# J_SD_KEYPAD.net
KiCad netlist of a schematic drawn in Altium Designer
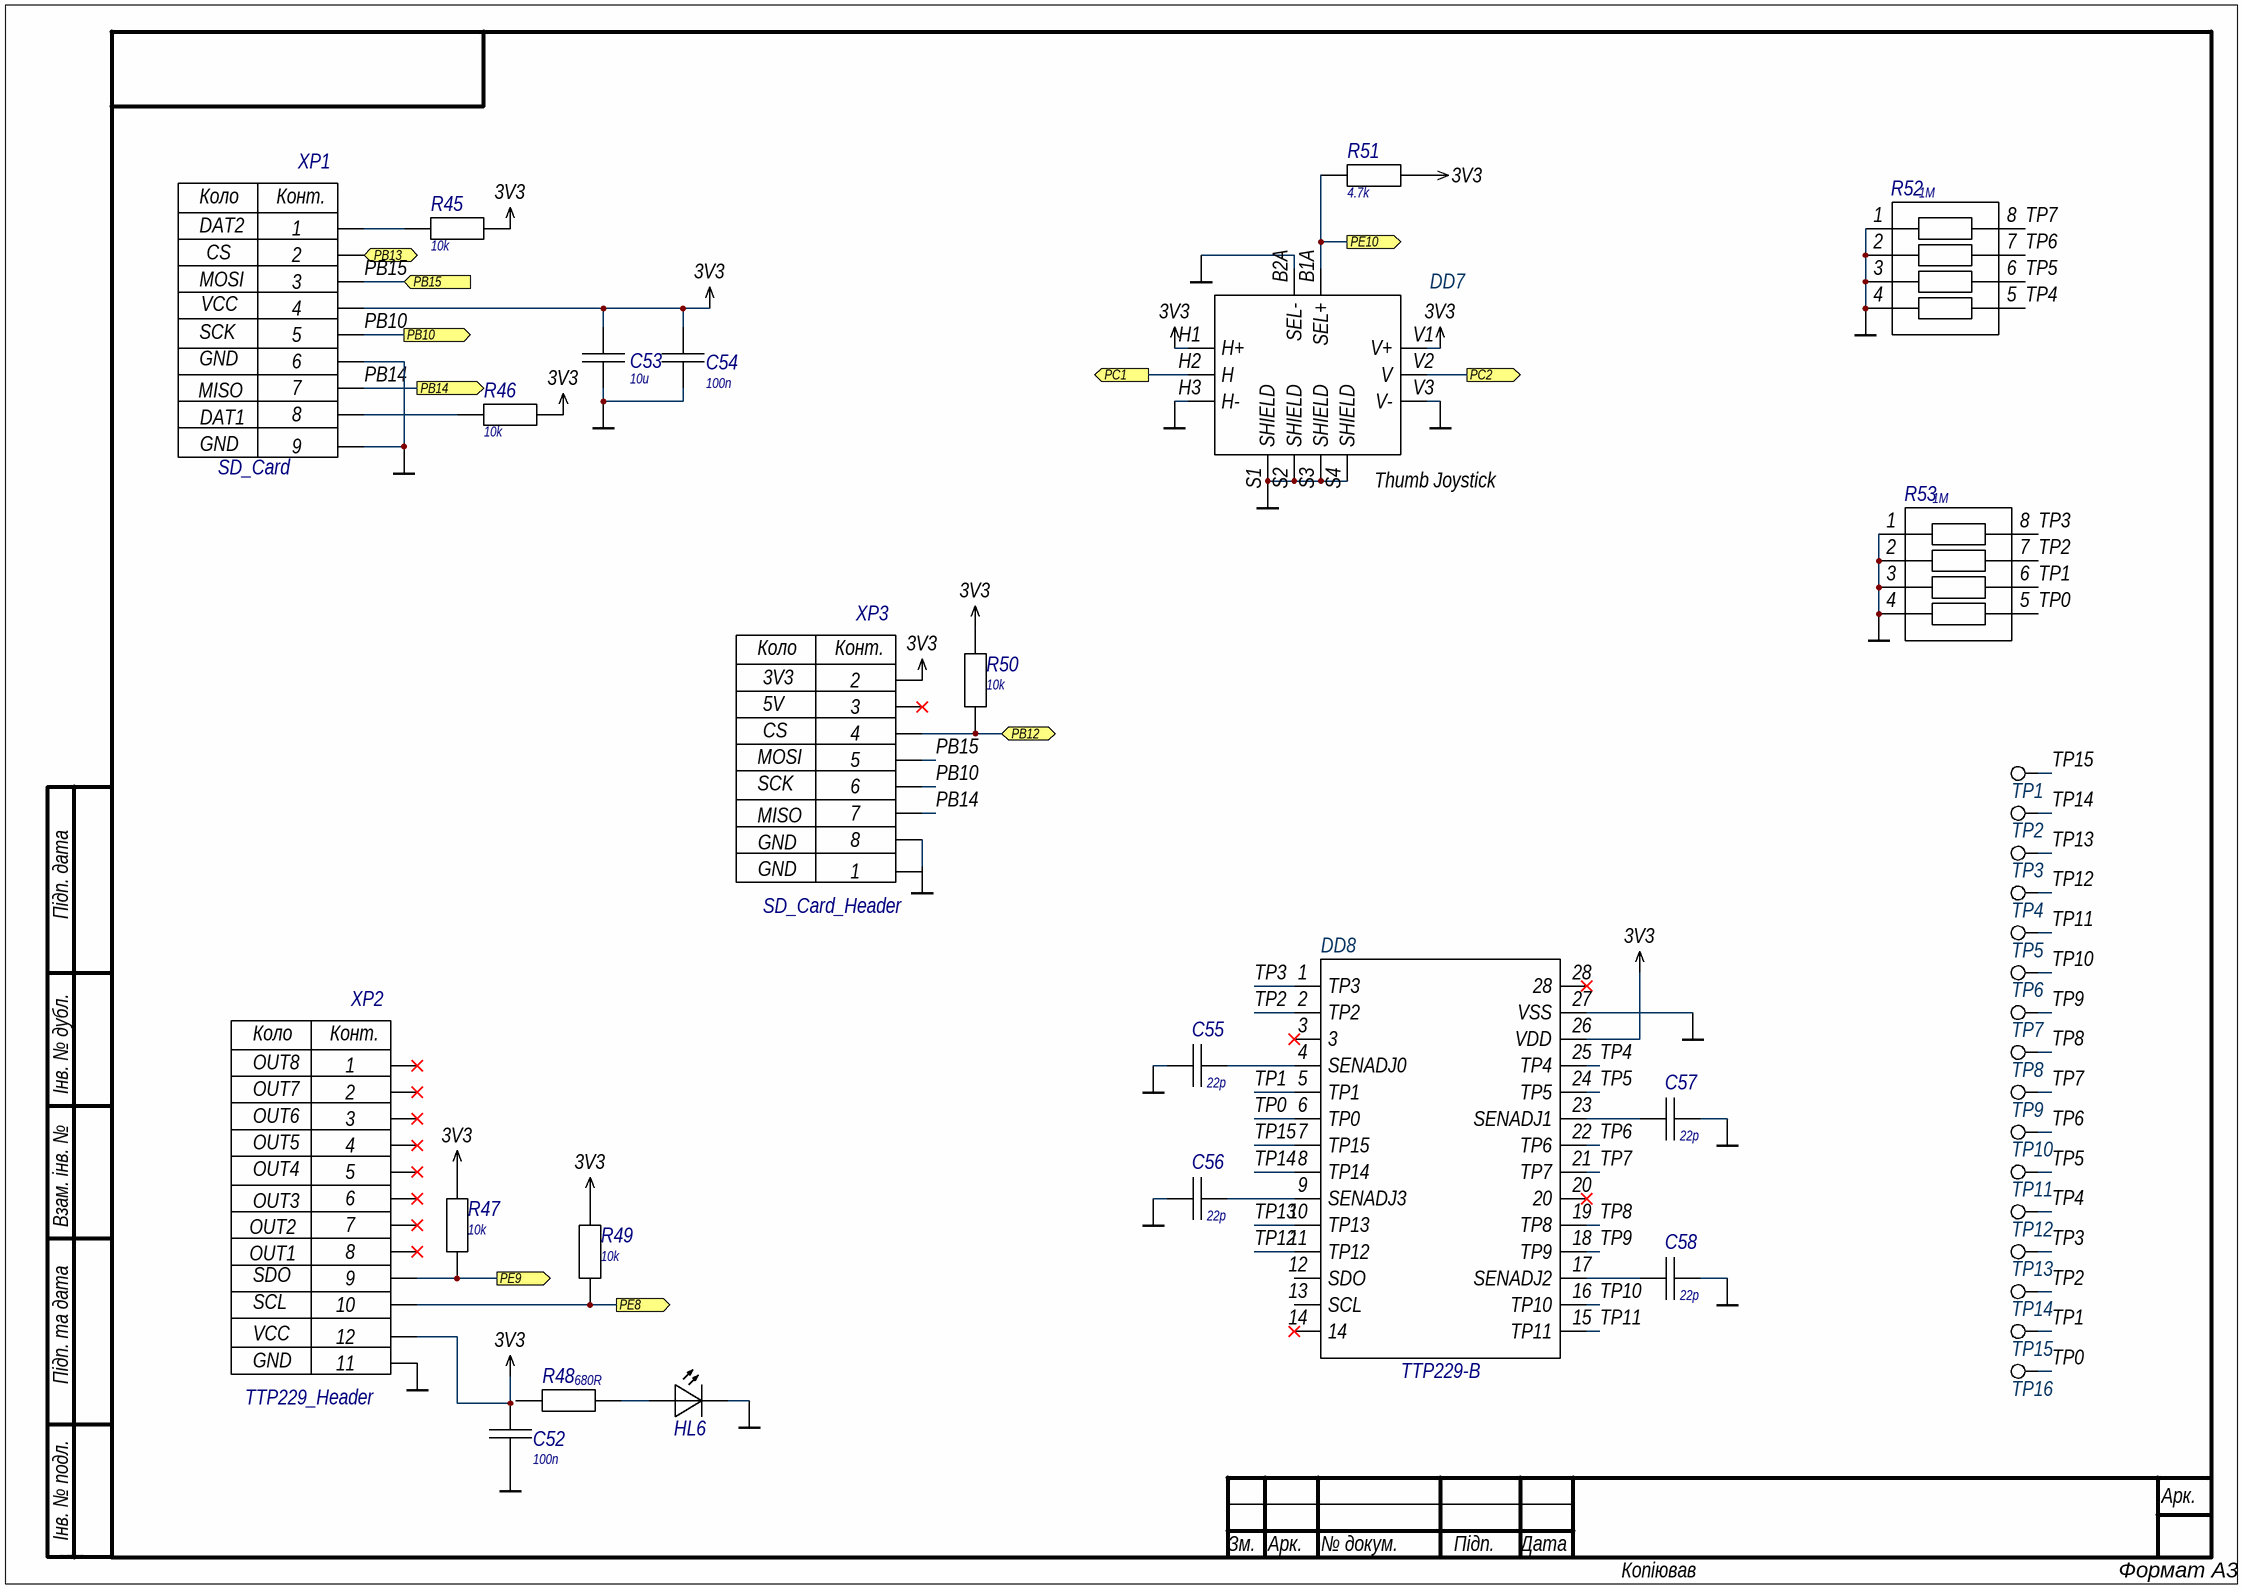
[diagram p0: J_SD_KEYPAD.SchDoc]

(export (version "E")
  (design (tool "Eeschema 10.0.6"))
  (components
    (comp (ref "C52")
      (value "100n")
      (footprint "C_0603")
      (fields
        (field (name "VOLTAGE") "50 В")
        (field (name "TOLERANCE") "10%")
        (field (name "MANUFACTURER") "TDK Corporation")
      )
      (libsource (lib "Schlib1") (part "C_0603"))
    )
    (comp (ref "C53")
      (value "10u")
      (footprint "C_0603")
      (fields
        (field (name "VOLTAGE") "50 В")
        (field (name "TOLERANCE") "10%")
        (field (name "MANUFACTURER") "TDK Corporation")
      )
      (libsource (lib "Schlib1") (part "C_0603"))
    )
    (comp (ref "C54")
      (value "100n")
      (footprint "C_0603")
      (fields
        (field (name "VOLTAGE") "50 В")
        (field (name "TOLERANCE") "10%")
        (field (name "MANUFACTURER") "TDK Corporation")
      )
      (libsource (lib "Schlib1") (part "C_0603"))
    )
    (comp (ref "C55")
      (value "22p")
      (footprint "C_0603")
      (fields
        (field (name "VOLTAGE") "50 В")
        (field (name "TOLERANCE") "10%")
        (field (name "MANUFACTURER") "TDK Corporation")
      )
      (libsource (lib "Schlib1") (part "C_0603"))
    )
    (comp (ref "C56")
      (value "22p")
      (footprint "C_0603")
      (fields
        (field (name "VOLTAGE") "50 В")
        (field (name "TOLERANCE") "10%")
        (field (name "MANUFACTURER") "TDK Corporation")
      )
      (libsource (lib "Schlib1") (part "C_0603"))
    )
    (comp (ref "C57")
      (value "22p")
      (footprint "C_0603")
      (fields
        (field (name "VOLTAGE") "50 В")
        (field (name "TOLERANCE") "10%")
        (field (name "MANUFACTURER") "TDK Corporation")
      )
      (libsource (lib "Schlib1") (part "C_0603"))
    )
    (comp (ref "C58")
      (value "22p")
      (footprint "C_0603")
      (fields
        (field (name "VOLTAGE") "50 В")
        (field (name "TOLERANCE") "10%")
        (field (name "MANUFACTURER") "TDK Corporation")
      )
      (libsource (lib "Schlib1") (part "C_0603"))
    )
    (comp (ref "DD7")
      (value "Thumb Joystick")
      (footprint "XDCR_COM-09032")
      (description "Thumb Joystick, 1568-09032-ND")
      (fields (field (name "MANUFACTURER") "SparkFun Electronics") (field (name "PART NUMBER") "COM-09032"))
      (libsource (lib "Schlib1") (part "COM-09032"))
    )
    (comp (ref "DD8")
      (value "CP2102-GM")
      (footprint "28-SSOP")
      (fields
        (field (name "MANUFACTURER") "Tontek Design Technology")
        (field (name "PART NUMBER") "TTP229-B")
      )
      (libsource (lib "Schlib1") (part "TTP229-B"))
    )
    (comp (ref "HL6")
      (value "XPEBFR-LS-0000-00A01")
      (footprint "LED")
      (fields (field (name "MANUFACTURER") "Cree LED"))
      (libsource (lib "Schlib1") (part "LED"))
    )
    (comp (ref "R45")
      (value "10k")
      (footprint "R0_0603")
      (fields
        (field (name "POWER") "0 В")
        (field (name "TOLERANCE") "1%")
        (field (name "MANUFACTURER") "Keystone Electronics")
      )
      (libsource (lib "") (part "R_0603_1"))
    )
    (comp (ref "R46")
      (value "10k")
      (footprint "R0_0603")
      (fields
        (field (name "POWER") "0 В")
        (field (name "TOLERANCE") "1%")
        (field (name "MANUFACTURER") "Keystone Electronics")
      )
      (libsource (lib "") (part "R_0603_1"))
    )
    (comp (ref "R47")
      (value "10k")
      (footprint "R0_0603")
      (fields
        (field (name "POWER") "0 В")
        (field (name "TOLERANCE") "1%")
        (field (name "MANUFACTURER") "Keystone Electronics")
      )
      (libsource (lib "Schlib1") (part "R_0603"))
    )
    (comp (ref "R48")
      (value "680R")
      (footprint "R0_0603")
      (fields
        (field (name "POWER") "0 В")
        (field (name "TOLERANCE") "1%")
        (field (name "MANUFACTURER") "Keystone Electronics")
      )
      (libsource (lib "") (part "R_0603_1"))
    )
    (comp (ref "R49")
      (value "10k")
      (footprint "R0_0603")
      (fields
        (field (name "POWER") "0 В")
        (field (name "TOLERANCE") "1%")
        (field (name "MANUFACTURER") "Keystone Electronics")
      )
      (libsource (lib "Schlib1") (part "R_0603"))
    )
    (comp (ref "R50")
      (value "10k")
      (footprint "R0_0603")
      (fields
        (field (name "POWER") "0 В")
        (field (name "TOLERANCE") "1%")
        (field (name "MANUFACTURER") "Keystone Electronics")
      )
      (libsource (lib "Schlib1") (part "R_0603"))
    )
    (comp (ref "R51")
      (value "4.7k")
      (footprint "R0_0603")
      (fields
        (field (name "POWER") "0 В")
        (field (name "TOLERANCE") "1%")
        (field (name "MANUFACTURER") "Keystone Electronics")
      )
      (libsource (lib "") (part "R_0603_1"))
    )
    (comp (ref "R52")
      (value "1M")
      (footprint "RESISTOR_NETWORKS")
      (fields
        (field (name "POWER") "0 В")
        (field (name "TOLERANCE") "1%")
        (field (name "MANUFACTURER") "Keystone Electronics")
      )
      (libsource (lib "Schlib1") (part "RESISTOR_NETWORKS"))
    )
    (comp (ref "R53")
      (value "1M")
      (footprint "RESISTOR_NETWORKS")
      (fields
        (field (name "POWER") "0 В")
        (field (name "TOLERANCE") "1%")
        (field (name "MANUFACTURER") "Keystone Electronics")
      )
      (libsource (lib "Schlib1") (part "RESISTOR_NETWORKS"))
    )
    (comp (ref "TP1")
      (value "TP")
      (footprint "PAD-1.25mm")
      (description "Test point 1.25mm. THT")
      (libsource (lib "Schlib1") (part "TP"))
    )
    (comp (ref "TP2")
      (value "TP")
      (footprint "PAD-1.25mm")
      (description "Test point 1.25mm. THT")
      (libsource (lib "Schlib1") (part "TP"))
    )
    (comp (ref "TP3")
      (value "TP")
      (footprint "PAD-1.25mm")
      (description "Test point 1.25mm. THT")
      (libsource (lib "Schlib1") (part "TP"))
    )
    (comp (ref "TP4")
      (value "TP")
      (footprint "PAD-1.25mm")
      (description "Test point 1.25mm. THT")
      (libsource (lib "Schlib1") (part "TP"))
    )
    (comp (ref "TP5")
      (value "TP")
      (footprint "PAD-1.25mm")
      (description "Test point 1.25mm. THT")
      (libsource (lib "Schlib1") (part "TP"))
    )
    (comp (ref "TP6")
      (value "TP")
      (footprint "PAD-1.25mm")
      (description "Test point 1.25mm. THT")
      (libsource (lib "Schlib1") (part "TP"))
    )
    (comp (ref "TP7")
      (value "TP")
      (footprint "PAD-1.25mm")
      (description "Test point 1.25mm. THT")
      (libsource (lib "Schlib1") (part "TP"))
    )
    (comp (ref "TP8")
      (value "TP")
      (footprint "PAD-1.25mm")
      (description "Test point 1.25mm. THT")
      (libsource (lib "Schlib1") (part "TP"))
    )
    (comp (ref "TP9")
      (value "TP")
      (footprint "PAD-1.25mm")
      (description "Test point 1.25mm. THT")
      (libsource (lib "Schlib1") (part "TP"))
    )
    (comp (ref "TP10")
      (value "TP")
      (footprint "PAD-1.25mm")
      (description "Test point 1.25mm. THT")
      (libsource (lib "Schlib1") (part "TP"))
    )
    (comp (ref "TP11")
      (value "TP")
      (footprint "PAD-1.25mm")
      (description "Test point 1.25mm. THT")
      (libsource (lib "Schlib1") (part "TP"))
    )
    (comp (ref "TP12")
      (value "TP")
      (footprint "PAD-1.25mm")
      (description "Test point 1.25mm. THT")
      (libsource (lib "Schlib1") (part "TP"))
    )
    (comp (ref "TP13")
      (value "TP")
      (footprint "PAD-1.25mm")
      (description "Test point 1.25mm. THT")
      (libsource (lib "Schlib1") (part "TP"))
    )
    (comp (ref "TP14")
      (value "TP")
      (footprint "PAD-1.25mm")
      (description "Test point 1.25mm. THT")
      (libsource (lib "Schlib1") (part "TP"))
    )
    (comp (ref "TP15")
      (value "TP")
      (footprint "PAD-1.25mm")
      (description "Test point 1.25mm. THT")
      (libsource (lib "Schlib1") (part "TP"))
    )
    (comp (ref "TP16")
      (value "TP")
      (footprint "PAD-1.25mm")
      (description "Test point 1.25mm. THT")
      (libsource (lib "Schlib1") (part "TP"))
    )
    (comp (ref "XP1")
      (value "SD_Card")
      (footprint "xp9")
      (description "475900001")
      (fields (field (name "MANUFACTURER") "Samtec Inc."))
      (libsource (lib "Schlib1") (part "9_PIN_HEADER"))
    )
    (comp (ref "XP2")
      (value "TTP229_Header")
      (footprint "xp12")
      (fields (field (name "MANUFACTURER") "Samtec Inc."))
      (libsource (lib "Schlib1") (part "12_PIN_HEADER"))
    )
    (comp (ref "XP3")
      (value "SD_Card_Header")
      (footprint "xp8")
      (description "475900001")
      (fields (field (name "MANUFACTURER") "Samtec Inc."))
      (libsource (lib "Schlib1") (part "8_PIN_HEADER"))
    )
  )
  (nets
    (net (code "1") (name "/PB10") (class "Default")
      (node (ref "XP1") (pin "5") (pinfunction "5_5") (pintype "passive"))
      (node (ref "XP3") (pin "6") (pinfunction "6_6") (pintype "passive"))
    )
    (net (code "2") (name "/PB12") (class "Default")
      (node (ref "R50") (pin "1") (pinfunction "1_1") (pintype "passive"))
      (node (ref "XP3") (pin "4") (pinfunction "4_4") (pintype "passive"))
    )
    (net (code "3") (name "/PB13") (class "Default")
      (node (ref "XP1") (pin "2") (pinfunction "2_2") (pintype "passive"))
    )
    (net (code "4") (name "/PB14") (class "Default")
      (node (ref "XP1") (pin "7") (pinfunction "7_7") (pintype "passive"))
      (node (ref "XP3") (pin "7") (pinfunction "7_7") (pintype "passive"))
    )
    (net (code "5") (name "/PB15") (class "Default")
      (node (ref "XP1") (pin "3") (pinfunction "3_3") (pintype "passive"))
      (node (ref "XP3") (pin "5") (pinfunction "5_5") (pintype "passive"))
    )
    (net (code "6") (name "/PC1") (class "Default")
      (node (ref "DD7") (pin "H2") (pinfunction "H_H2") (pintype "passive"))
    )
    (net (code "7") (name "/PC2") (class "Default")
      (node (ref "DD7") (pin "V2") (pinfunction "V_V2") (pintype "passive"))
    )
    (net (code "8") (name "/PE8") (class "Default")
      (node (ref "R49") (pin "1") (pinfunction "1_1") (pintype "passive"))
      (node (ref "XP2") (pin "10") (pinfunction "10_10") (pintype "passive"))
    )
    (net (code "9") (name "/PE9") (class "Default")
      (node (ref "R47") (pin "1") (pinfunction "1_1") (pintype "passive"))
      (node (ref "XP2") (pin "9") (pinfunction "9_9") (pintype "passive"))
    )
    (net (code "10") (name "/PE10") (class "Default")
      (node (ref "DD7") (pin "B1A") (pinfunction "SEL+_B1A") (pintype "passive"))
      (node (ref "R51") (pin "1") (pinfunction "1_1") (pintype "passive"))
    )
    (net (code "11") (name "/TP0") (class "Default")
      (node (ref "DD8") (pin "6") (pinfunction "TP0_6") (pintype "passive"))
      (node (ref "R53") (pin "5") (pinfunction "5_5") (pintype "passive"))
      (node (ref "TP16") (pin "1") (pinfunction "1_1") (pintype "passive"))
    )
    (net (code "12") (name "/TP1") (class "Default")
      (node (ref "DD8") (pin "5") (pinfunction "TP1_5") (pintype "passive"))
      (node (ref "R53") (pin "6") (pinfunction "6_6") (pintype "passive"))
      (node (ref "TP15") (pin "1") (pinfunction "1_1") (pintype "passive"))
    )
    (net (code "13") (name "/TP2") (class "Default")
      (node (ref "DD8") (pin "2") (pinfunction "TP2_2") (pintype "passive"))
      (node (ref "R53") (pin "7") (pinfunction "7_7") (pintype "passive"))
      (node (ref "TP14") (pin "1") (pinfunction "1_1") (pintype "passive"))
    )
    (net (code "14") (name "/TP3") (class "Default")
      (node (ref "DD8") (pin "1") (pinfunction "TP3_1") (pintype "passive"))
      (node (ref "R53") (pin "8") (pinfunction "8_8") (pintype "passive"))
      (node (ref "TP13") (pin "1") (pinfunction "1_1") (pintype "passive"))
    )
    (net (code "15") (name "/TP4") (class "Default")
      (node (ref "DD8") (pin "25") (pinfunction "TP4_25") (pintype "passive"))
      (node (ref "R52") (pin "5") (pinfunction "5_5") (pintype "passive"))
      (node (ref "TP12") (pin "1") (pinfunction "1_1") (pintype "passive"))
    )
    (net (code "16") (name "/TP5") (class "Default")
      (node (ref "DD8") (pin "24") (pinfunction "TP5_24") (pintype "passive"))
      (node (ref "R52") (pin "6") (pinfunction "6_6") (pintype "passive"))
      (node (ref "TP11") (pin "1") (pinfunction "1_1") (pintype "passive"))
    )
    (net (code "17") (name "/TP6") (class "Default")
      (node (ref "DD8") (pin "22") (pinfunction "TP6_22") (pintype "passive"))
      (node (ref "R52") (pin "7") (pinfunction "7_7") (pintype "passive"))
      (node (ref "TP10") (pin "1") (pinfunction "1_1") (pintype "passive"))
    )
    (net (code "18") (name "/TP7") (class "Default")
      (node (ref "DD8") (pin "21") (pinfunction "TP7_21") (pintype "passive"))
      (node (ref "R52") (pin "8") (pinfunction "8_8") (pintype "passive"))
      (node (ref "TP9") (pin "1") (pinfunction "1_1") (pintype "passive"))
    )
    (net (code "19") (name "/TP8") (class "Default")
      (node (ref "DD8") (pin "19") (pinfunction "TP8_19") (pintype "passive"))
      (node (ref "TP8") (pin "1") (pinfunction "1_1") (pintype "passive"))
    )
    (net (code "20") (name "/TP9") (class "Default")
      (node (ref "DD8") (pin "18") (pinfunction "TP9_18") (pintype "passive"))
      (node (ref "TP7") (pin "1") (pinfunction "1_1") (pintype "passive"))
    )
    (net (code "21") (name "/TP10") (class "Default")
      (node (ref "DD8") (pin "16") (pinfunction "TP10_16") (pintype "passive"))
      (node (ref "TP6") (pin "1") (pinfunction "1_1") (pintype "passive"))
    )
    (net (code "22") (name "/TP11") (class "Default")
      (node (ref "DD8") (pin "15") (pinfunction "TP11_15") (pintype "passive"))
      (node (ref "TP5") (pin "1") (pinfunction "1_1") (pintype "passive"))
    )
    (net (code "23") (name "/TP12") (class "Default")
      (node (ref "DD8") (pin "11") (pinfunction "TP12_11") (pintype "passive"))
      (node (ref "TP4") (pin "1") (pinfunction "1_1") (pintype "passive"))
    )
    (net (code "24") (name "/TP13") (class "Default")
      (node (ref "DD8") (pin "10") (pinfunction "TP13_10") (pintype "passive"))
      (node (ref "TP3") (pin "1") (pinfunction "1_1") (pintype "passive"))
    )
    (net (code "25") (name "/TP14") (class "Default")
      (node (ref "DD8") (pin "8") (pinfunction "TP14_8") (pintype "passive"))
      (node (ref "TP2") (pin "1") (pinfunction "1_1") (pintype "passive"))
    )
    (net (code "26") (name "/TP15") (class "Default")
      (node (ref "DD8") (pin "7") (pinfunction "TP15_7") (pintype "passive"))
      (node (ref "TP1") (pin "1") (pinfunction "1_1") (pintype "passive"))
    )
    (net (code "27") (name "3V3") (class "Default")
      (node (ref "C52") (pin "1") (pinfunction "1_1") (pintype "passive"))
      (node (ref "C53") (pin "2") (pinfunction "2_2") (pintype "passive"))
      (node (ref "C54") (pin "2") (pinfunction "2_2") (pintype "passive"))
      (node (ref "DD7") (pin "H1") (pinfunction "H+_H1") (pintype "passive"))
      (node (ref "DD7") (pin "V1") (pinfunction "V+_V1") (pintype "passive"))
      (node (ref "DD8") (pin "26") (pinfunction "VDD_26") (pintype "passive"))
      (node (ref "R45") (pin "2") (pinfunction "2_2") (pintype "passive"))
      (node (ref "R46") (pin "2") (pinfunction "2_2") (pintype "passive"))
      (node (ref "R47") (pin "2") (pinfunction "2_2") (pintype "passive"))
      (node (ref "R49") (pin "2") (pinfunction "2_2") (pintype "passive"))
      (node (ref "R50") (pin "2") (pinfunction "2_2") (pintype "passive"))
      (node (ref "R51") (pin "2") (pinfunction "2_2") (pintype "passive"))
      (node (ref "XP1") (pin "4") (pinfunction "4_4") (pintype "passive"))
      (node (ref "XP2") (pin "12") (pinfunction "12_12") (pintype "passive"))
      (node (ref "XP3") (pin "2") (pinfunction "2_2") (pintype "passive"))
    )
    (net (code "28") (name "GND") (class "Default")
      (node (ref "C52") (pin "2") (pinfunction "2_2") (pintype "passive"))
      (node (ref "C53") (pin "1") (pinfunction "1_1") (pintype "passive"))
      (node (ref "C54") (pin "1") (pinfunction "1_1") (pintype "passive"))
      (node (ref "C55") (pin "1") (pinfunction "1_1") (pintype "passive"))
      (node (ref "C56") (pin "1") (pinfunction "1_1") (pintype "passive"))
      (node (ref "C57") (pin "2") (pinfunction "2_2") (pintype "passive"))
      (node (ref "C58") (pin "2") (pinfunction "2_2") (pintype "passive"))
      (node (ref "DD7") (pin "B2A") (pinfunction "SEL-_B2A") (pintype "passive"))
      (node (ref "DD7") (pin "H3") (pinfunction "H-_H3") (pintype "passive"))
      (node (ref "DD7") (pin "S1") (pinfunction "SHIELD_S1") (pintype "passive"))
      (node (ref "DD7") (pin "S2") (pinfunction "SHIELD_S2") (pintype "passive"))
      (node (ref "DD7") (pin "S3") (pinfunction "SHIELD_S3") (pintype "passive"))
      (node (ref "DD7") (pin "S4") (pinfunction "SHIELD_S4") (pintype "passive"))
      (node (ref "DD7") (pin "V3") (pinfunction "V-_V3") (pintype "passive"))
      (node (ref "DD8") (pin "27") (pinfunction "VSS_27") (pintype "passive"))
      (node (ref "HL6") (pin "2") (pinfunction "2_2") (pintype "passive"))
      (node (ref "R52") (pin "1") (pinfunction "1_1") (pintype "passive"))
      (node (ref "R52") (pin "2") (pinfunction "2_2") (pintype "passive"))
      (node (ref "R52") (pin "3") (pinfunction "3_3") (pintype "passive"))
      (node (ref "R52") (pin "4") (pinfunction "4_4") (pintype "passive"))
      (node (ref "R53") (pin "1") (pinfunction "1_1") (pintype "passive"))
      (node (ref "R53") (pin "2") (pinfunction "2_2") (pintype "passive"))
      (node (ref "R53") (pin "3") (pinfunction "3_3") (pintype "passive"))
      (node (ref "R53") (pin "4") (pinfunction "4_4") (pintype "passive"))
      (node (ref "XP1") (pin "6") (pinfunction "6_6") (pintype "passive"))
      (node (ref "XP1") (pin "9") (pinfunction "9_9") (pintype "passive"))
      (node (ref "XP2") (pin "11") (pinfunction "11_11") (pintype "passive"))
      (node (ref "XP3") (pin "8") (pinfunction "8_8") (pintype "passive"))
    )
    (net (code "29") (name "Net-(DD8-SENADJ0)") (class "Default")
      (node (ref "C55") (pin "2") (pinfunction "2_2") (pintype "passive"))
      (node (ref "DD8") (pin "4") (pinfunction "SENADJ0_4") (pintype "passive"))
    )
    (net (code "30") (name "Net-(DD8-SENADJ1)") (class "Default")
      (node (ref "C57") (pin "1") (pinfunction "1_1") (pintype "passive"))
      (node (ref "DD8") (pin "23") (pinfunction "SENADJ1_23") (pintype "passive"))
    )
    (net (code "31") (name "Net-(DD8-SENADJ2)") (class "Default")
      (node (ref "C58") (pin "1") (pinfunction "1_1") (pintype "passive"))
      (node (ref "DD8") (pin "17") (pinfunction "SENADJ2_17") (pintype "passive"))
    )
    (net (code "32") (name "Net-(DD8-SENADJ3)") (class "Default")
      (node (ref "C56") (pin "2") (pinfunction "2_2") (pintype "passive"))
      (node (ref "DD8") (pin "9") (pinfunction "SENADJ3_9") (pintype "passive"))
    )
    (net (code "33") (name "Net-(HL6-Pad1)") (class "Default")
      (node (ref "HL6") (pin "1") (pinfunction "1_1") (pintype "passive"))
      (node (ref "R48") (pin "2") (pinfunction "2_2") (pintype "passive"))
    )
    (net (code "34") (name "Net-(R45-Pad1)") (class "Default")
      (node (ref "R45") (pin "1") (pinfunction "1_1") (pintype "passive"))
      (node (ref "XP1") (pin "1") (pinfunction "1_1") (pintype "passive"))
    )
    (net (code "35") (name "Net-(R46-Pad1)") (class "Default")
      (node (ref "R46") (pin "1") (pinfunction "1_1") (pintype "passive"))
      (node (ref "XP1") (pin "8") (pinfunction "8_8") (pintype "passive"))
    )
    (net (code "36") (name "unconnected-(DD8-Pad3)") (class "Default")
      (node (ref "DD8") (pin "3") (pinfunction "3_3") (pintype "passive+no_connect"))
    )
    (net (code "37") (name "unconnected-(DD8-Pad14)") (class "Default")
      (node (ref "DD8") (pin "14") (pinfunction "14_14") (pintype "passive+no_connect"))
    )
    (net (code "38") (name "unconnected-(DD8-Pad20)") (class "Default")
      (node (ref "DD8") (pin "20") (pinfunction "20_20") (pintype "passive+no_connect"))
    )
    (net (code "39") (name "unconnected-(DD8-Pad28)") (class "Default")
      (node (ref "DD8") (pin "28") (pinfunction "28_28") (pintype "passive+no_connect"))
    )
    (net (code "40") (name "unconnected-(DD8-SCL-Pad13)") (class "Default")
      (node (ref "DD8") (pin "13") (pinfunction "SCL_13") (pintype "passive"))
    )
    (net (code "41") (name "unconnected-(DD8-SDO-Pad12)") (class "Default")
      (node (ref "DD8") (pin "12") (pinfunction "SDO_12") (pintype "passive"))
    )
    (net (code "42") (name "unconnected-(R48-Pad1)") (class "Default")
      (node (ref "R48") (pin "1") (pinfunction "1_1") (pintype "passive"))
    )
    (net (code "43") (name "unconnected-(XP2-Pad1)") (class "Default")
      (node (ref "XP2") (pin "1") (pinfunction "1_1") (pintype "passive+no_connect"))
    )
    (net (code "44") (name "unconnected-(XP2-Pad2)") (class "Default")
      (node (ref "XP2") (pin "2") (pinfunction "2_2") (pintype "passive+no_connect"))
    )
    (net (code "45") (name "unconnected-(XP2-Pad3)") (class "Default")
      (node (ref "XP2") (pin "3") (pinfunction "3_3") (pintype "passive+no_connect"))
    )
    (net (code "46") (name "unconnected-(XP2-Pad4)") (class "Default")
      (node (ref "XP2") (pin "4") (pinfunction "4_4") (pintype "passive+no_connect"))
    )
    (net (code "47") (name "unconnected-(XP2-Pad5)") (class "Default")
      (node (ref "XP2") (pin "5") (pinfunction "5_5") (pintype "passive+no_connect"))
    )
    (net (code "48") (name "unconnected-(XP2-Pad6)") (class "Default")
      (node (ref "XP2") (pin "6") (pinfunction "6_6") (pintype "passive+no_connect"))
    )
    (net (code "49") (name "unconnected-(XP2-Pad7)") (class "Default")
      (node (ref "XP2") (pin "7") (pinfunction "7_7") (pintype "passive+no_connect"))
    )
    (net (code "50") (name "unconnected-(XP2-Pad8)") (class "Default")
      (node (ref "XP2") (pin "8") (pinfunction "8_8") (pintype "passive+no_connect"))
    )
    (net (code "51") (name "unconnected-(XP3-Pad1)") (class "Default")
      (node (ref "XP3") (pin "1") (pinfunction "1_1") (pintype "passive"))
    )
    (net (code "52") (name "unconnected-(XP3-Pad3)") (class "Default")
      (node (ref "XP3") (pin "3") (pinfunction "3_3") (pintype "passive+no_connect"))
    )
  )
)
